# CAN.net
KiCad netlist of a schematic drawn in Altium Designer
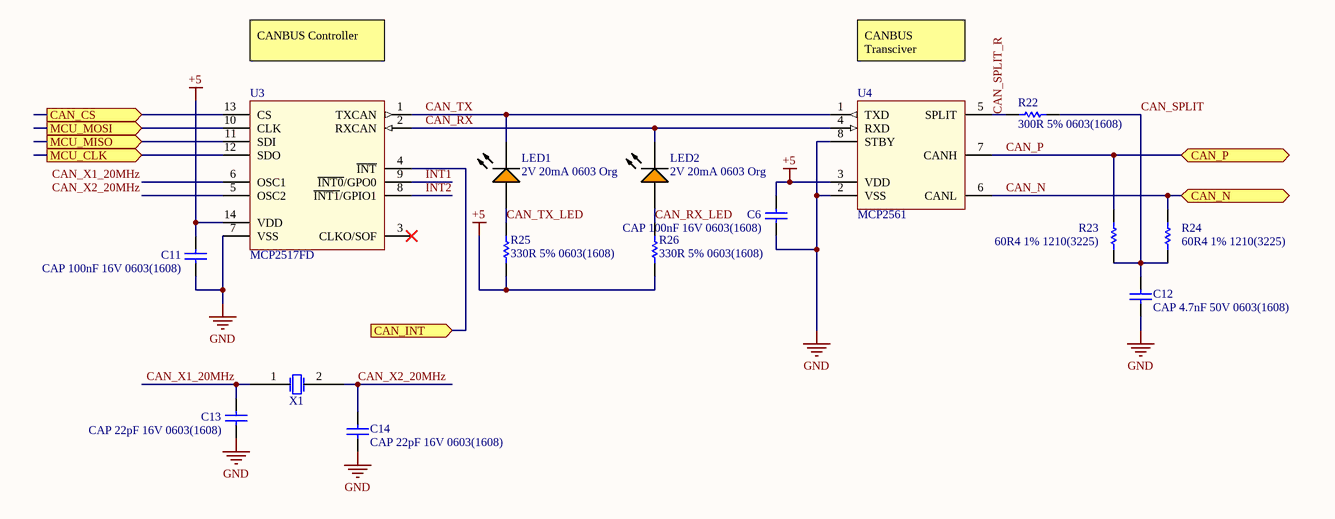
[diagram p0: CAN.SchDoc]

(export (version "E")
  (design (tool "Eeschema 10.0.6"))
  (components
    (comp (ref "C6")
      (value "CAP 100nF 16V 0603(1608)")
      (footprint "CAPC0603(1608)100_N")
      (description "CAP 100nF 16V ±10% 0603 (1608 Metric) Thickness 1mm SMD")
      (fields (field (name "TOLERANCE") "Â±10%"))
      (libsource (lib "Altium Content Vault") (part "CAP"))
    )
    (comp (ref "C11")
      (value "CAP 100nF 16V 0603(1608)")
      (footprint "CAPC0603(1608)100_N")
      (description "CAP 100nF 16V ±10% 0603 (1608 Metric) Thickness 1mm SMD")
      (fields (field (name "TOLERANCE") "Â±10%"))
      (libsource (lib "Altium Content Vault") (part "CAP"))
    )
    (comp (ref "C12")
      (value "CAP 4.7nF 50V 0603(1608)")
      (footprint "CAPC0603(1608)100_M")
      (description "CAP 4.7nF 50V ±5% 0603 (1608 Metric) Thickness 1mm SMD")
      (fields (field (name "TOLERANCE") "Â±5%"))
      (libsource (lib "Altium Content Vault") (part "CAP"))
    )
    (comp (ref "C13")
      (value "CAP 22pF 16V 0603(1608)")
      (footprint "CAPC0603(1608)100_N")
      (description "CAP 22pF 16V ±5% 0603 (1608 Metric) Thickness 1mm SMD")
      (fields (field (name "TOLERANCE") "Â±5%"))
      (libsource (lib "Altium Content Vault") (part "CAP"))
    )
    (comp (ref "C14")
      (value "CAP 22pF 16V 0603(1608)")
      (footprint "CAPC0603(1608)100_N")
      (description "CAP 22pF 16V ±5% 0603 (1608 Metric) Thickness 1mm SMD")
      (fields (field (name "TOLERANCE") "Â±5%"))
      (libsource (lib "Altium Content Vault") (part "CAP"))
    )
    (comp (ref "LED1")
      (value "2V 20mA 0603 Org")
      (footprint "KING-LED0603-25-ORANGE_V")
      (description "LED, SMT, 0603(1608), 0.25mm Tthickness, Super Bright Orange")
      (fields (field (name "PARTNUMBER") "APG1608SEKC/T"))
      (libsource (lib "Altium Content Vault") (part "KING-LED_ORANGE_A1K2-2"))
    )
    (comp (ref "LED2")
      (value "2V 20mA 0603 Org")
      (footprint "KING-LED0603-25-ORANGE_V")
      (description "LED, SMT, 0603(1608), 0.25mm Tthickness, Super Bright Orange")
      (fields (field (name "PARTNUMBER") "APG1608SEKC/T"))
      (libsource (lib "Altium Content Vault") (part "KING-LED_ORANGE_A1K2-2"))
    )
    (comp (ref "R22")
      (value "300R 5% 0603(1608)")
      (footprint "RESC0603(1608)_N")
      (description "300R 0.1W 5% 0603 (1608 Metric)  SMD")
      (fields (field (name "TOLERANCE") "5 %") (field (name "POWER") "0.1 W"))
      (libsource (lib "Altium Content Vault") (part "RES"))
    )
    (comp (ref "R23")
      (value "60R4 1% 1210(3225)")
      (footprint "RESC1210(3225)_L")
      (description "60R4 0.5W 1% 1210 (3225 Metric)  SMD")
      (fields (field (name "TOLERANCE") "1 %") (field (name "POWER") "0.5 W"))
      (libsource (lib "Altium Content Vault") (part "RES"))
    )
    (comp (ref "R24")
      (value "60R4 1% 1210(3225)")
      (footprint "RESC1210(3225)_L")
      (description "60R4 0.5W 1% 1210 (3225 Metric)  SMD")
      (fields (field (name "TOLERANCE") "1 %") (field (name "POWER") "0.5 W"))
      (libsource (lib "Altium Content Vault") (part "RES"))
    )
    (comp (ref "R25")
      (value "330R 5% 0603(1608)")
      (footprint "RESC0603(1608)_L")
      (description "330R 0.1W 5% 0603 (1608 Metric)  SMD")
      (fields (field (name "TOLERANCE") "5 %") (field (name "POWER") "0.1 W"))
      (libsource (lib "Altium Content Vault") (part "RES"))
    )
    (comp (ref "R26")
      (value "330R 5% 0603(1608)")
      (footprint "RESC0603(1608)_L")
      (description "330R 0.1W 5% 0603 (1608 Metric)  SMD")
      (fields (field (name "TOLERANCE") "5 %") (field (name "POWER") "0.1 W"))
      (libsource (lib "Altium Content Vault") (part "RES"))
    )
    (comp (ref "U3")
      (value "MCP2517FD")
      (footprint "MCP2517FD SOIC")
      (libsource (lib "QUTMS_CANLibrary") (part "MCP2517FD"))
    )
    (comp (ref "U4")
      (value "MCP2561")
      (footprint "MCP2561 SOIC")
      (libsource (lib "QUTMS_CANLibrary") (part "MCP2561"))
    )
    (comp (ref "X1")
      (value "Crystal 20MHz")
      (footprint "Crystal 20MHz")
      (libsource (lib "QUTMS_CrystalLibrary") (part "Crystal 20MHz"))
    )
  )
  (nets
    (net (code "1") (name "+5") (class "Default")
      (node (ref "C11") (pin "2") (pinfunction "2_2") (pintype "passive"))
      (node (ref "C6") (pin "2") (pinfunction "2_2") (pintype "passive"))
      (node (ref "R25") (pin "1") (pinfunction "1_1") (pintype "passive"))
      (node (ref "R26") (pin "1") (pinfunction "1_1") (pintype "passive"))
      (node (ref "U3") (pin "14") (pinfunction "VDD_14") (pintype "passive"))
      (node (ref "U4") (pin "3") (pinfunction "VDD_3") (pintype "passive"))
    )
    (net (code "2") (name "/CAN_CS") (class "Default")
      (node (ref "U3") (pin "13") (pinfunction "CS_13") (pintype "passive"))
    )
    (net (code "3") (name "/CAN_INT") (class "Default")
      (node (ref "U3") (pin "4") (pinfunction "~{INT}_4") (pintype "passive"))
    )
    (net (code "4") (name "/CAN_N") (class "Default")
      (node (ref "R24") (pin "2") (pinfunction "2_2") (pintype "passive"))
      (node (ref "U4") (pin "6") (pinfunction "CANL_6") (pintype "passive"))
    )
    (net (code "5") (name "/CAN_P") (class "Default")
      (node (ref "R23") (pin "2") (pinfunction "2_2") (pintype "passive"))
      (node (ref "U4") (pin "7") (pinfunction "CANH_7") (pintype "passive"))
    )
    (net (code "6") (name "/CAN_RX") (class "Default")
      (node (ref "LED2") (pin "2") (pinfunction "K_2") (pintype "passive"))
      (node (ref "U3") (pin "2") (pinfunction "RXCAN_2") (pintype "input"))
      (node (ref "U4") (pin "4") (pinfunction "RXD_4") (pintype "input"))
    )
    (net (code "7") (name "/CAN_RX_LED") (class "Default")
      (node (ref "LED2") (pin "1") (pinfunction "A_1") (pintype "passive"))
      (node (ref "R26") (pin "2") (pinfunction "2_2") (pintype "passive"))
    )
    (net (code "8") (name "/CAN_SPLIT") (class "Default")
      (node (ref "C12") (pin "2") (pinfunction "2_2") (pintype "passive"))
      (node (ref "R22") (pin "2") (pinfunction "2_2") (pintype "passive"))
      (node (ref "R23") (pin "1") (pinfunction "1_1") (pintype "passive"))
      (node (ref "R24") (pin "1") (pinfunction "1_1") (pintype "passive"))
    )
    (net (code "9") (name "/CAN_SPLIT_R") (class "Default")
      (node (ref "R22") (pin "1") (pinfunction "1_1") (pintype "passive"))
      (node (ref "U4") (pin "5") (pinfunction "SPLIT_5") (pintype "passive"))
    )
    (net (code "10") (name "/CAN_TX") (class "Default")
      (node (ref "LED1") (pin "2") (pinfunction "K_2") (pintype "passive"))
      (node (ref "U3") (pin "1") (pinfunction "TXCAN_1") (pintype "output"))
      (node (ref "U4") (pin "1") (pinfunction "TXD_1") (pintype "output"))
    )
    (net (code "11") (name "/CAN_TX_LED") (class "Default")
      (node (ref "LED1") (pin "1") (pinfunction "A_1") (pintype "passive"))
      (node (ref "R25") (pin "2") (pinfunction "2_2") (pintype "passive"))
    )
    (net (code "12") (name "/CAN_X1_20MHz") (class "Default")
      (node (ref "C13") (pin "2") (pinfunction "2_2") (pintype "passive"))
      (node (ref "U3") (pin "6") (pinfunction "OSC1_6") (pintype "passive"))
      (node (ref "X1") (pin "1") (pintype "passive"))
    )
    (net (code "13") (name "/CAN_X2_20MHz") (class "Default")
      (node (ref "C14") (pin "1") (pinfunction "1_1") (pintype "passive"))
      (node (ref "U3") (pin "5") (pinfunction "OSC2_5") (pintype "passive"))
      (node (ref "X1") (pin "2") (pintype "passive"))
    )
    (net (code "14") (name "/INT1") (class "Default")
      (node (ref "U3") (pin "9") (pinfunction "~{INT0}/GPO0_9") (pintype "passive"))
    )
    (net (code "15") (name "/INT2") (class "Default")
      (node (ref "U3") (pin "8") (pinfunction "~{INT1}/GPIO1_8") (pintype "passive"))
    )
    (net (code "16") (name "/MCU_CLK") (class "Default")
      (node (ref "U3") (pin "12") (pinfunction "SDO_12") (pintype "passive"))
    )
    (net (code "17") (name "/MCU_MISO") (class "Default")
      (node (ref "U3") (pin "11") (pinfunction "SDI_11") (pintype "passive"))
    )
    (net (code "18") (name "/MCU_MOSI") (class "Default")
      (node (ref "U3") (pin "10") (pinfunction "CLK_10") (pintype "passive"))
    )
    (net (code "19") (name "GND") (class "Default")
      (node (ref "C11") (pin "1") (pinfunction "1_1") (pintype "passive"))
      (node (ref "C12") (pin "1") (pinfunction "1_1") (pintype "passive"))
      (node (ref "C13") (pin "1") (pinfunction "1_1") (pintype "passive"))
      (node (ref "C14") (pin "2") (pinfunction "2_2") (pintype "passive"))
      (node (ref "C6") (pin "1") (pinfunction "1_1") (pintype "passive"))
      (node (ref "U3") (pin "7") (pinfunction "VSS_7") (pintype "passive"))
      (node (ref "U4") (pin "2") (pinfunction "VSS_2") (pintype "passive"))
      (node (ref "U4") (pin "8") (pinfunction "STBY_8") (pintype "passive"))
    )
    (net (code "20") (name "unconnected-(U3-CLKO{slash}SOF-Pad3)") (class "Default")
      (node (ref "U3") (pin "3") (pinfunction "CLKO/SOF_3") (pintype "passive+no_connect"))
    )
  )
)
